# MezzanineConnectors.net
KiCad netlist of a schematic drawn in Altium Designer
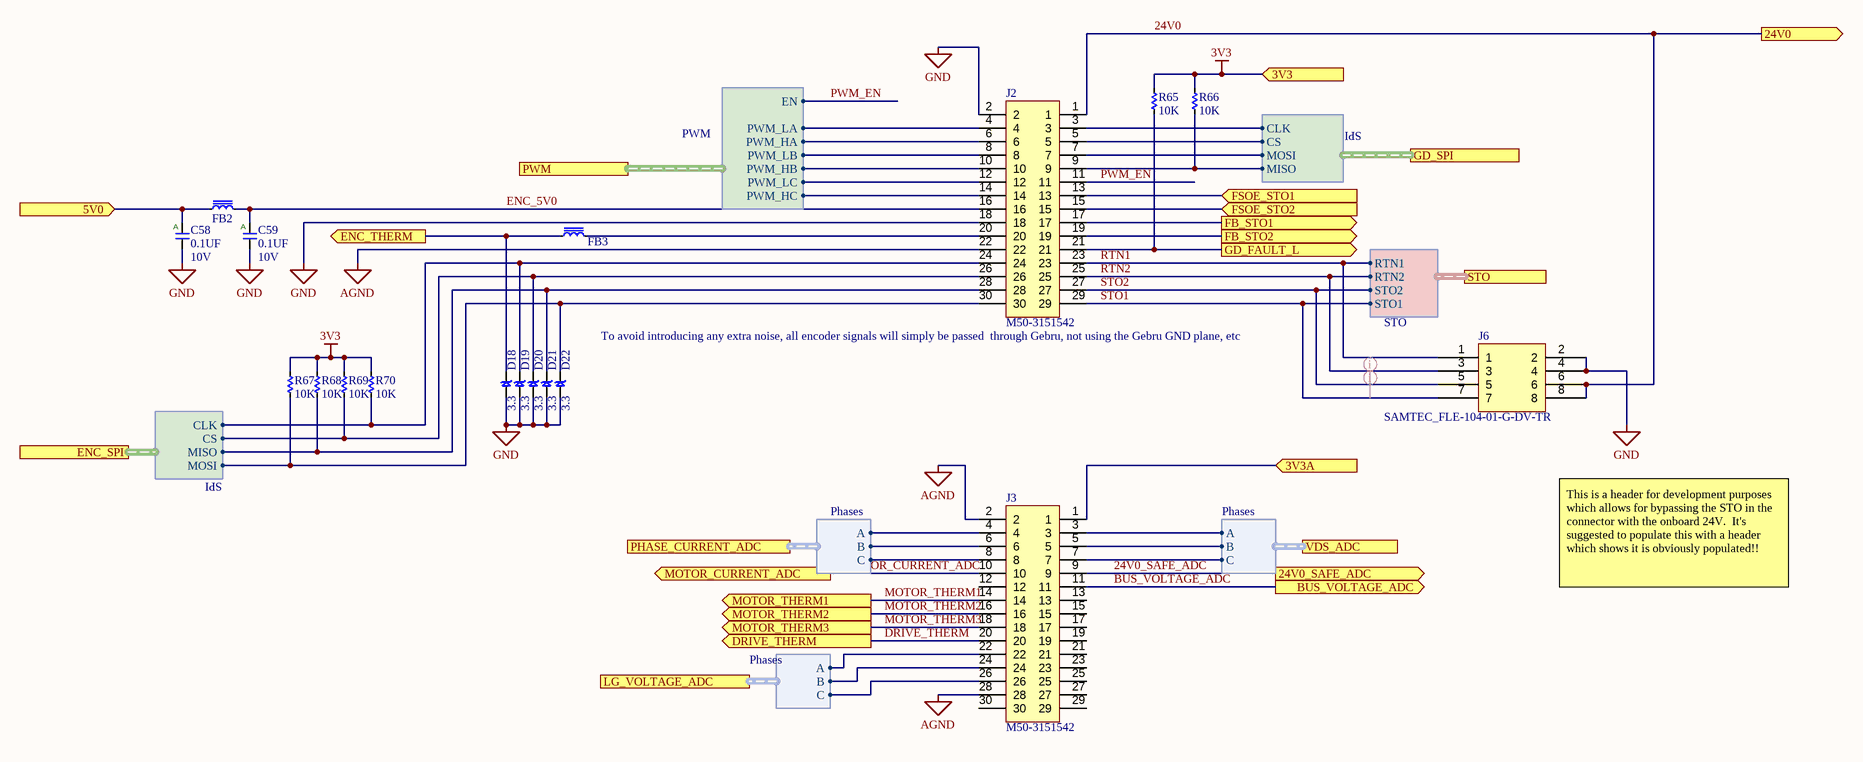
[diagram p0: MezzanineConnectors.SchDoc]

(export (version "E")
  (design (tool "Eeschema 10.0.6"))
  (components
    (comp (ref "C58")
      (value "0.1UF")
      (footprint "C0201Y")
      (description "CAP, CER, X6S, 0.1uF, 10V, 10%, 0201, AUTOGRADE")
      (fields (field (name "MFG") "MURATA") (field (name "VOLTAGE") "10V") (field (name "TOLERANCE") "10%"))
      (libsource (lib "AltiumReleaseLibDB") (part "__Template_Cap_Auto"))
    )
    (comp (ref "C59")
      (value "0.1UF")
      (footprint "C0201Y")
      (description "CAP, CER, X6S, 0.1uF, 10V, 10%, 0201, AUTOGRADE")
      (fields (field (name "MFG") "MURATA") (field (name "VOLTAGE") "10V") (field (name "TOLERANCE") "10%"))
      (libsource (lib "AltiumReleaseLibDB") (part "__Template_Cap_Auto"))
    )
    (comp (ref "D18")
      (value "3.3")
      (footprint "SOD1060X40")
      (description "TVS, DIODE, UNIDIR, 3.3VRWM, 4.8VBR, 7.8VCL, SOD-923")
      (fields (field (name "MFG") "ON Semiconductor"))
      (libsource (lib "AltiumReleaseLibDB") (part "__Template_Diode_TVS_A/K"))
    )
    (comp (ref "D19")
      (value "3.3")
      (footprint "SOD1060X40")
      (description "TVS, DIODE, UNIDIR, 3.3VRWM, 4.8VBR, 7.8VCL, SOD-923")
      (fields (field (name "MFG") "ON Semiconductor"))
      (libsource (lib "AltiumReleaseLibDB") (part "__Template_Diode_TVS_A/K"))
    )
    (comp (ref "D20")
      (value "3.3")
      (footprint "SOD1060X40")
      (description "TVS, DIODE, UNIDIR, 3.3VRWM, 4.8VBR, 7.8VCL, SOD-923")
      (fields (field (name "MFG") "ON Semiconductor"))
      (libsource (lib "AltiumReleaseLibDB") (part "__Template_Diode_TVS_A/K"))
    )
    (comp (ref "D21")
      (value "3.3")
      (footprint "SOD1060X40")
      (description "TVS, DIODE, UNIDIR, 3.3VRWM, 4.8VBR, 7.8VCL, SOD-923")
      (fields (field (name "MFG") "ON Semiconductor"))
      (libsource (lib "AltiumReleaseLibDB") (part "__Template_Diode_TVS_A/K"))
    )
    (comp (ref "D22")
      (value "3.3")
      (footprint "SOD1060X40")
      (description "TVS, DIODE, UNIDIR, 3.3VRWM, 4.8VBR, 7.8VCL, SOD-923")
      (fields (field (name "MFG") "ON Semiconductor"))
      (libsource (lib "AltiumReleaseLibDB") (part "__Template_Diode_TVS_A/K"))
    )
    (comp (ref "FB2")
      (value "LAIRD MI0603L221R-10")
      (footprint "INDC160X80X105L30N")
      (description "LAIRD - MI0603L221R-10 - Ferrite Bead, 0603 [1608 Metric], 220 ohm, 2 A, MI Series, 0.05 ohm")
      (fields
        (field (name "MANUFACTURER") "Laird Technologies")
        (field (name "MANUFACTURER PART NUMBER") "MI0603L221R-10")
      )
      (libsource (lib "MiscSch1") (part "LAIRD_MI0603L221R-10"))
    )
    (comp (ref "FB3")
      (value "LAIRD MI0603L221R-10")
      (footprint "INDC160X80X105L30N")
      (description "LAIRD - MI0603L221R-10 - Ferrite Bead, 0603 [1608 Metric], 220 ohm, 2 A, MI Series, 0.05 ohm")
      (fields
        (field (name "MANUFACTURER") "Laird Technologies")
        (field (name "MANUFACTURER PART NUMBER") "MI0603L221R-10")
      )
      (libsource (lib "MiscSch1") (part "LAIRD_MI0603L221R-10"))
    )
    (comp (ref "J2")
      (value "~")
      (footprint "HARWIN_M50-3151542")
      (description "CONN, RCPT, FEMALE, 30 P, 1.27MM, 2.45MM H, GOLD, SMD")
      (fields (field (name "MFG") "Harwin Inc.") (field (name "MFG P/N") "M50-3151542"))
      (libsource (lib "AltiumReleaseLibDB") (part "__Template_Connector_2X15"))
    )
    (comp (ref "J3")
      (value "~")
      (footprint "HARWIN_M50-3151542")
      (description "CONN, RCPT, FEMALE, 30 P, 1.27MM, 2.45MM H, GOLD, SMD")
      (fields (field (name "MFG") "Harwin Inc.") (field (name "MFG P/N") "M50-3151542"))
      (libsource (lib "AltiumReleaseLibDB") (part "__Template_Connector_2X15"))
    )
    (comp (ref "J6")
      (value "SAMTEC_FLE-104-01-G-DV-TR")
      (footprint "SAMTEC_FLE-104-01-G-DV-TR")
      (description "CONN RCPT .05\" 8POS DUAL SMD")
      (fields
        (field (name "MANUFACTURER") "Samtec")
        (field (name "MANUFACTURER PART NUMBER") "FLE-104-01-G-DV")
      )
      (libsource (lib "MiscSch1") (part "SAMTEC_FLE-104-01-G-DV-TR"))
    )
    (comp (ref "R65")
      (value "10K")
      (footprint "R0201_H0.26MM")
      (description "RES, 10K, 1%, 1/20W, 0201, AUTOGRADE")
      (fields (field (name "MFG") "PANASONIC") (field (name "POWER") "1/20W"))
      (libsource (lib "AltiumReleaseLibDB") (part "__Template_Resistor"))
    )
    (comp (ref "R66")
      (value "10K")
      (footprint "R0201_H0.26MM")
      (description "RES, 10K, 1%, 1/20W, 0201, AUTOGRADE")
      (fields (field (name "MFG") "PANASONIC") (field (name "POWER") "1/20W"))
      (libsource (lib "AltiumReleaseLibDB") (part "__Template_Resistor"))
    )
    (comp (ref "R67")
      (value "10K")
      (footprint "R0201_H0.26MM")
      (description "RES, 10K, 1%, 1/20W, 0201, AUTOGRADE")
      (fields (field (name "MFG") "PANASONIC") (field (name "POWER") "1/20W"))
      (libsource (lib "AltiumReleaseLibDB") (part "__Template_Resistor"))
    )
    (comp (ref "R68")
      (value "10K")
      (footprint "R0201_H0.26MM")
      (description "RES, 10K, 1%, 1/20W, 0201, AUTOGRADE")
      (fields (field (name "MFG") "PANASONIC") (field (name "POWER") "1/20W"))
      (libsource (lib "AltiumReleaseLibDB") (part "__Template_Resistor"))
    )
    (comp (ref "R69")
      (value "10K")
      (footprint "R0201_H0.26MM")
      (description "RES, 10K, 1%, 1/20W, 0201, AUTOGRADE")
      (fields (field (name "MFG") "PANASONIC") (field (name "POWER") "1/20W"))
      (libsource (lib "AltiumReleaseLibDB") (part "__Template_Resistor"))
    )
    (comp (ref "R70")
      (value "10K")
      (footprint "R0201_H0.26MM")
      (description "RES, 10K, 1%, 1/20W, 0201, AUTOGRADE")
      (fields (field (name "MFG") "PANASONIC") (field (name "POWER") "1/20W"))
      (libsource (lib "AltiumReleaseLibDB") (part "__Template_Resistor"))
    )
  )
  (nets
    (net (code "5") (name "/3V3A") (class "Default")
      (node (ref "J3") (pin "1") (pinfunction "1_1") (pintype "passive"))
    )
    (net (code "6") (name "/5V0") (class "Default")
      (node (ref "C58") (pin "1") (pintype "passive"))
      (node (ref "FB2") (pin "1") (pintype "passive"))
    )
    (net (code "7") (name "/24V0") (class "Default")
      (node (ref "J2") (pin "1") (pinfunction "1_1") (pintype "passive"))
      (node (ref "J6") (pin "6") (pinfunction "6_6") (pintype "passive"))
      (node (ref "J6") (pin "8") (pinfunction "8_8") (pintype "passive"))
    )
    (net (code "8") (name "/24V0_SAFE_ADC") (class "Default")
      (node (ref "J3") (pin "9") (pinfunction "9_9") (pintype "passive"))
    )
    (net (code "9") (name "/BUS_VOLTAGE_ADC") (class "Default")
      (node (ref "J3") (pin "11") (pinfunction "11_11") (pintype "passive"))
    )
    (net (code "10") (name "/DRIVE_THERM") (class "Default")
      (node (ref "J3") (pin "20") (pinfunction "20_20") (pintype "passive"))
    )
    (net (code "11") (name "/ENC_5V0") (class "Default")
      (node (ref "C59") (pin "1") (pintype "passive"))
      (node (ref "FB2") (pin "2") (pintype "passive"))
      (node (ref "J2") (pin "16") (pinfunction "16_16") (pintype "passive"))
    )
    (net (code "12") (name "/ENC_THERM") (class "Default")
      (node (ref "D18") (pin "K") (pinfunction "K_K") (pintype "passive"))
      (node (ref "FB3") (pin "1") (pintype "passive"))
    )
    (net (code "13") (name "/FB_STO1") (class "Default")
      (node (ref "J2") (pin "17") (pinfunction "17_17") (pintype "passive"))
    )
    (net (code "14") (name "/FB_STO2") (class "Default")
      (node (ref "J2") (pin "19") (pinfunction "19_19") (pintype "passive"))
    )
    (net (code "15") (name "/FSOE_STO1") (class "Default")
      (node (ref "J2") (pin "13") (pinfunction "13_13") (pintype "passive"))
    )
    (net (code "16") (name "/FSOE_STO2") (class "Default")
      (node (ref "J2") (pin "15") (pinfunction "15_15") (pintype "passive"))
    )
    (net (code "17") (name "/GD_FAULT_L") (class "Default")
      (node (ref "J2") (pin "21") (pinfunction "21_21") (pintype "passive"))
      (node (ref "R65") (pin "1") (pintype "passive"))
    )
    (net (code "18") (name "/MOTOR_CURRENT_ADC") (class "Default")
      (node (ref "J3") (pin "10") (pinfunction "10_10") (pintype "passive"))
    )
    (net (code "19") (name "/MOTOR_THERM1") (class "Default")
      (node (ref "J3") (pin "14") (pinfunction "14_14") (pintype "passive"))
    )
    (net (code "20") (name "/MOTOR_THERM2") (class "Default")
      (node (ref "J3") (pin "16") (pinfunction "16_16") (pintype "passive"))
    )
    (net (code "21") (name "/MOTOR_THERM3") (class "Default")
      (node (ref "J3") (pin "18") (pinfunction "18_18") (pintype "passive"))
    )
    (net (code "22") (name "/PWM_EN") (class "Default")
      (node (ref "J2") (pin "11") (pinfunction "11_11") (pintype "passive"))
    )
    (net (code "23") (name "/PWM_HA") (class "Default")
      (node (ref "J2") (pin "6") (pinfunction "6_6") (pintype "passive"))
    )
    (net (code "24") (name "/PWM_HB") (class "Default")
      (node (ref "J2") (pin "10") (pinfunction "10_10") (pintype "passive"))
    )
    (net (code "25") (name "/PWM_HC") (class "Default")
      (node (ref "J2") (pin "14") (pinfunction "14_14") (pintype "passive"))
    )
    (net (code "26") (name "/PWM_LA") (class "Default")
      (node (ref "J2") (pin "4") (pinfunction "4_4") (pintype "passive"))
    )
    (net (code "27") (name "/PWM_LB") (class "Default")
      (node (ref "J2") (pin "8") (pinfunction "8_8") (pintype "passive"))
    )
    (net (code "28") (name "/PWM_LC") (class "Default")
      (node (ref "J2") (pin "12") (pinfunction "12_12") (pintype "passive"))
    )
    (net (code "29") (name "/RTN1") (class "Default")
      (node (ref "J2") (pin "23") (pinfunction "23_23") (pintype "passive"))
      (node (ref "J6") (pin "1") (pinfunction "1_1") (pintype "passive"))
    )
    (net (code "30") (name "/RTN2") (class "Default")
      (node (ref "J2") (pin "25") (pinfunction "25_25") (pintype "passive"))
      (node (ref "J6") (pin "3") (pinfunction "3_3") (pintype "passive"))
    )
    (net (code "31") (name "/STO1") (class "Default")
      (node (ref "J2") (pin "29") (pinfunction "29_29") (pintype "passive"))
      (node (ref "J6") (pin "7") (pinfunction "7_7") (pintype "passive"))
    )
    (net (code "32") (name "/STO2") (class "Default")
      (node (ref "J2") (pin "27") (pinfunction "27_27") (pintype "passive"))
      (node (ref "J6") (pin "5") (pinfunction "5_5") (pintype "passive"))
    )
    (net (code "37") (name "3V3") (class "Default")
      (node (ref "R65") (pin "2") (pintype "passive"))
      (node (ref "R66") (pin "2") (pintype "passive"))
      (node (ref "R67") (pin "2") (pintype "passive"))
      (node (ref "R68") (pin "2") (pintype "passive"))
      (node (ref "R69") (pin "2") (pintype "passive"))
      (node (ref "R70") (pin "2") (pintype "passive"))
    )
    (net (code "38") (name "AGND") (class "Default")
      (node (ref "J2") (pin "22") (pinfunction "22_22") (pintype "passive"))
      (node (ref "J3") (pin "2") (pinfunction "2_2") (pintype "passive"))
      (node (ref "J3") (pin "28") (pinfunction "28_28") (pintype "passive"))
    )
    (net (code "39") (name "GND") (class "Default")
      (node (ref "C58") (pin "2") (pintype "passive"))
      (node (ref "C59") (pin "2") (pintype "passive"))
      (node (ref "D18") (pin "A") (pinfunction "A_A") (pintype "passive"))
      (node (ref "D19") (pin "A") (pinfunction "A_A") (pintype "passive"))
      (node (ref "D20") (pin "A") (pinfunction "A_A") (pintype "passive"))
      (node (ref "D21") (pin "A") (pinfunction "A_A") (pintype "passive"))
      (node (ref "D22") (pin "A") (pinfunction "A_A") (pintype "passive"))
      (node (ref "J2") (pin "18") (pinfunction "18_18") (pintype "passive"))
      (node (ref "J2") (pin "2") (pinfunction "2_2") (pintype "passive"))
      (node (ref "J6") (pin "2") (pinfunction "2_2") (pintype "passive"))
      (node (ref "J6") (pin "4") (pinfunction "4_4") (pintype "passive"))
    )
    (net (code "40") (name "Net-(D19-PadK)") (class "Default")
      (node (ref "D19") (pin "K") (pinfunction "K_K") (pintype "passive"))
      (node (ref "J2") (pin "24") (pinfunction "24_24") (pintype "passive"))
      (node (ref "R70") (pin "1") (pintype "passive"))
    )
    (net (code "41") (name "Net-(D20-PadK)") (class "Default")
      (node (ref "D20") (pin "K") (pinfunction "K_K") (pintype "passive"))
      (node (ref "J2") (pin "26") (pinfunction "26_26") (pintype "passive"))
      (node (ref "R69") (pin "1") (pintype "passive"))
    )
    (net (code "42") (name "Net-(D21-PadK)") (class "Default")
      (node (ref "D21") (pin "K") (pinfunction "K_K") (pintype "passive"))
      (node (ref "J2") (pin "28") (pinfunction "28_28") (pintype "passive"))
      (node (ref "R68") (pin "1") (pintype "passive"))
    )
    (net (code "43") (name "Net-(D22-PadK)") (class "Default")
      (node (ref "D22") (pin "K") (pinfunction "K_K") (pintype "passive"))
      (node (ref "J2") (pin "30") (pinfunction "30_30") (pintype "passive"))
      (node (ref "R67") (pin "1") (pintype "passive"))
    )
    (net (code "44") (name "Net-(FB3-Pad2)") (class "Default")
      (node (ref "FB3") (pin "2") (pintype "passive"))
      (node (ref "J2") (pin "20") (pinfunction "20_20") (pintype "passive"))
    )
    (net (code "45") (name "Net-(J2-Pad9)") (class "Default")
      (node (ref "J2") (pin "9") (pinfunction "9_9") (pintype "passive"))
      (node (ref "R66") (pin "1") (pintype "passive"))
    )
    (net (code "46") (name "unconnected-(J2-Pad3)") (class "Default")
      (node (ref "J2") (pin "3") (pinfunction "3_3") (pintype "passive"))
    )
    (net (code "47") (name "unconnected-(J2-Pad5)") (class "Default")
      (node (ref "J2") (pin "5") (pinfunction "5_5") (pintype "passive"))
    )
    (net (code "48") (name "unconnected-(J2-Pad7)") (class "Default")
      (node (ref "J2") (pin "7") (pinfunction "7_7") (pintype "passive"))
    )
    (net (code "49") (name "unconnected-(J3-Pad3)") (class "Default")
      (node (ref "J3") (pin "3") (pinfunction "3_3") (pintype "passive"))
    )
    (net (code "50") (name "unconnected-(J3-Pad4)") (class "Default")
      (node (ref "J3") (pin "4") (pinfunction "4_4") (pintype "passive"))
    )
    (net (code "51") (name "unconnected-(J3-Pad5)") (class "Default")
      (node (ref "J3") (pin "5") (pinfunction "5_5") (pintype "passive"))
    )
    (net (code "52") (name "unconnected-(J3-Pad6)") (class "Default")
      (node (ref "J3") (pin "6") (pinfunction "6_6") (pintype "passive"))
    )
    (net (code "53") (name "unconnected-(J3-Pad7)") (class "Default")
      (node (ref "J3") (pin "7") (pinfunction "7_7") (pintype "passive"))
    )
    (net (code "54") (name "unconnected-(J3-Pad8)") (class "Default")
      (node (ref "J3") (pin "8") (pinfunction "8_8") (pintype "passive"))
    )
    (net (code "55") (name "unconnected-(J3-Pad12)") (class "Default")
      (node (ref "J3") (pin "12") (pinfunction "12_12") (pintype "passive"))
    )
    (net (code "56") (name "unconnected-(J3-Pad13)") (class "Default")
      (node (ref "J3") (pin "13") (pinfunction "13_13") (pintype "passive"))
    )
    (net (code "57") (name "unconnected-(J3-Pad15)") (class "Default")
      (node (ref "J3") (pin "15") (pinfunction "15_15") (pintype "passive"))
    )
    (net (code "58") (name "unconnected-(J3-Pad17)") (class "Default")
      (node (ref "J3") (pin "17") (pinfunction "17_17") (pintype "passive"))
    )
    (net (code "59") (name "unconnected-(J3-Pad19)") (class "Default")
      (node (ref "J3") (pin "19") (pinfunction "19_19") (pintype "passive"))
    )
    (net (code "60") (name "unconnected-(J3-Pad21)") (class "Default")
      (node (ref "J3") (pin "21") (pinfunction "21_21") (pintype "passive"))
    )
    (net (code "61") (name "unconnected-(J3-Pad22)") (class "Default")
      (node (ref "J3") (pin "22") (pinfunction "22_22") (pintype "passive"))
    )
    (net (code "62") (name "unconnected-(J3-Pad23)") (class "Default")
      (node (ref "J3") (pin "23") (pinfunction "23_23") (pintype "passive"))
    )
    (net (code "63") (name "unconnected-(J3-Pad24)") (class "Default")
      (node (ref "J3") (pin "24") (pinfunction "24_24") (pintype "passive"))
    )
    (net (code "64") (name "unconnected-(J3-Pad25)") (class "Default")
      (node (ref "J3") (pin "25") (pinfunction "25_25") (pintype "passive"))
    )
    (net (code "65") (name "unconnected-(J3-Pad26)") (class "Default")
      (node (ref "J3") (pin "26") (pinfunction "26_26") (pintype "passive"))
    )
    (net (code "66") (name "unconnected-(J3-Pad27)") (class "Default")
      (node (ref "J3") (pin "27") (pinfunction "27_27") (pintype "passive"))
    )
    (net (code "67") (name "unconnected-(J3-Pad29)") (class "Default")
      (node (ref "J3") (pin "29") (pinfunction "29_29") (pintype "passive"))
    )
    (net (code "68") (name "unconnected-(J3-Pad30)") (class "Default")
      (node (ref "J3") (pin "30") (pinfunction "30_30") (pintype "passive"))
    )
  )
)
